# switch-pth-20mm-mk-1_0.net
KiCad netlist of a schematic drawn in EAGLE
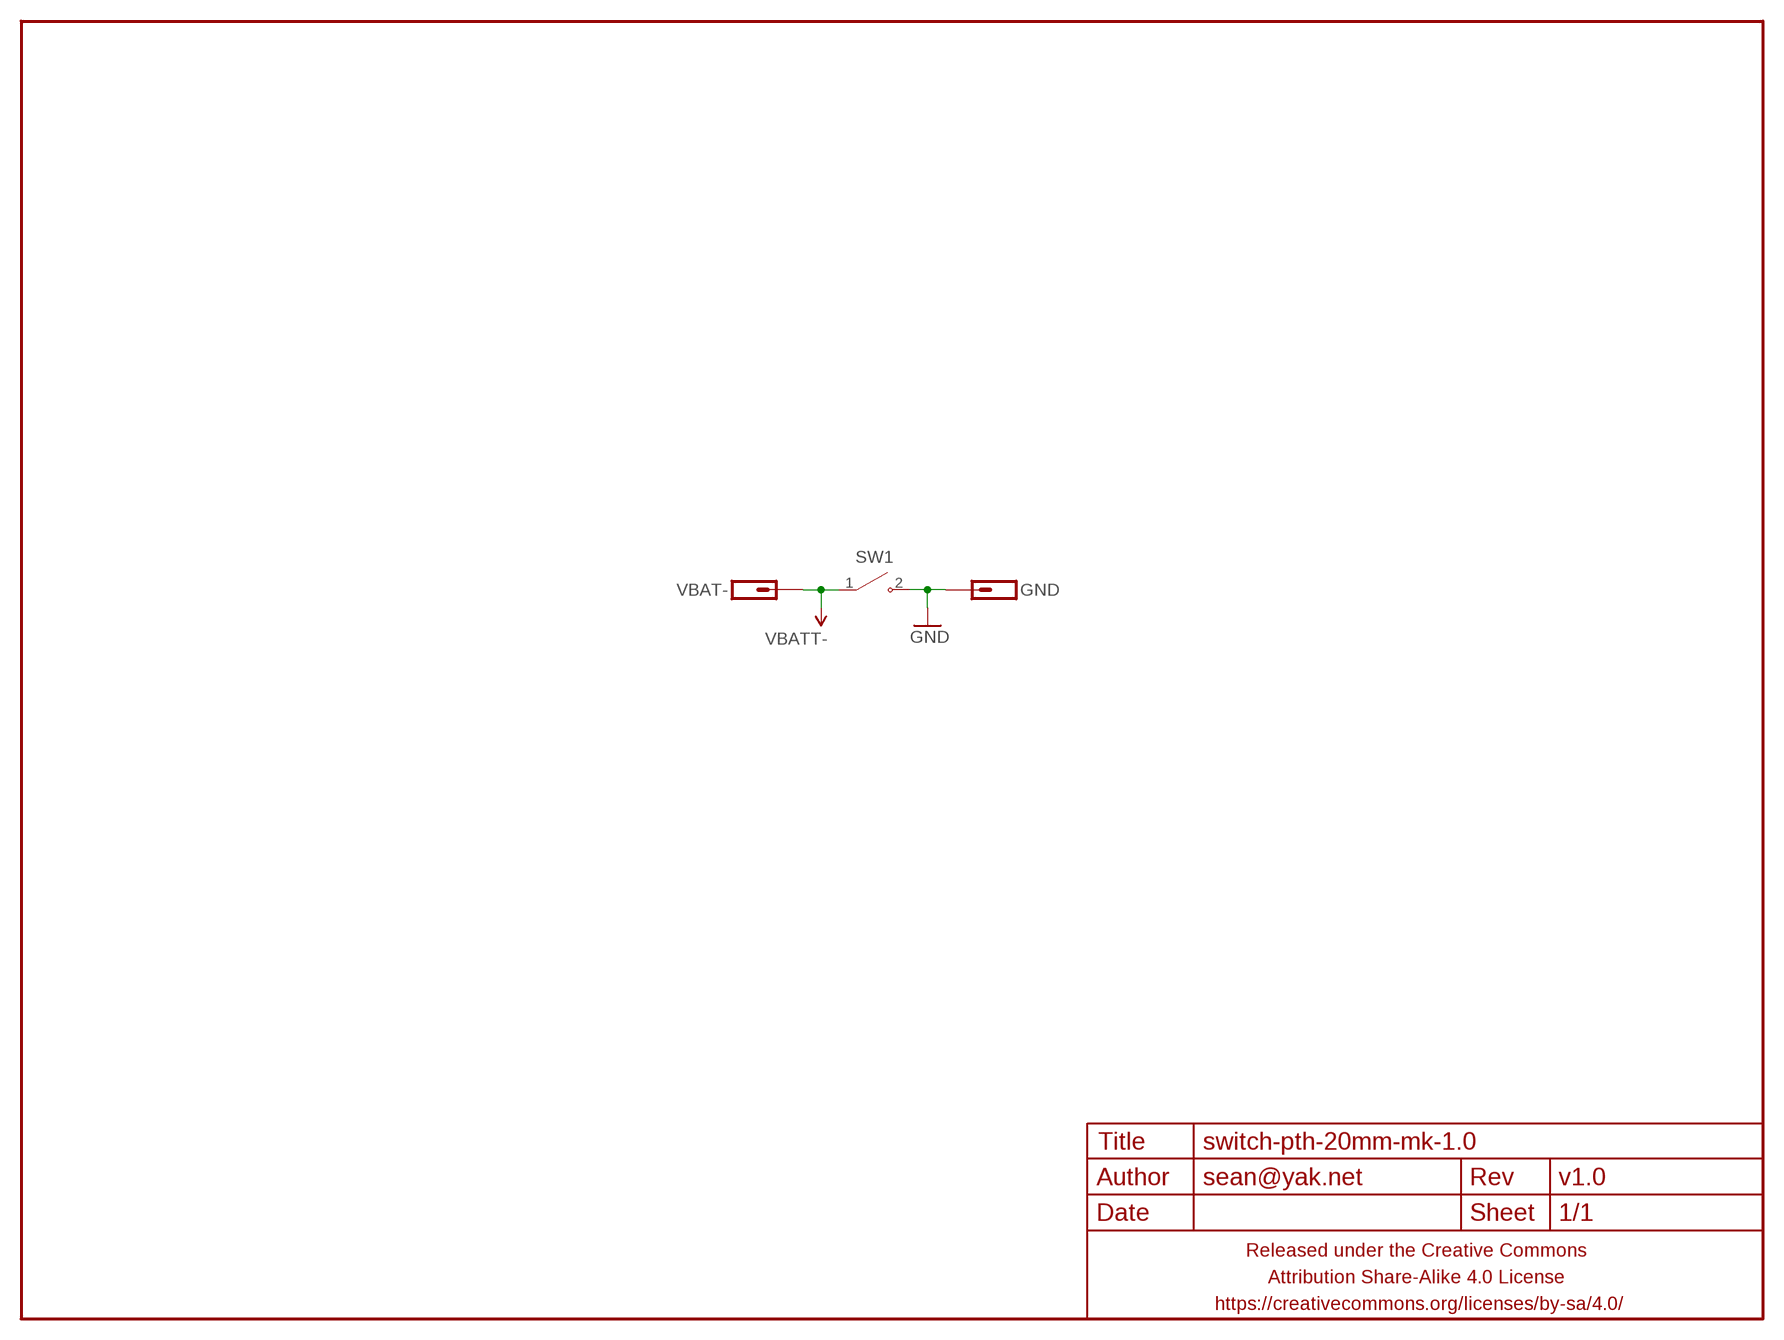
[diagram p0: schematic, sheet 1]

(export (version "E")
  (design (tool "Eeschema 10.0.6"))
  (components
    (comp (ref "FRAME1")
      (value "FRAME-LETTERNO_PACKAGE")
      (footprint "eagle-import:DUMMY")
      (fields (field (name "DESIGNER") "sean@yak.net") (field (name "VERSION") "v1.0"))
      (libsource (lib "eagle-import") (part "FRAME-LETTERNO_PACKAGE"))
    )
    (comp (ref "GND")
      (value "M01NOT-A-VIA-NOPE")
      (footprint "eagle-import:1X01_NOSILK_NOSTOP")
      (libsource (lib "eagle-import") (part "M01NOT-A-VIA-NOPE"))
    )
    (comp (ref "SW1")
      (value "SWITCH-SPSTOMTEN-1288-PTH")
      (footprint "eagle-import:OMTEN-1288-PTH")
      (libsource (lib "eagle-import") (part "SWITCH-SPSTOMTEN-1288-PTH"))
    )
    (comp (ref "VBAT-")
      (value "M01PTH-1MM-CIR-NS")
      (footprint "eagle-import:1X01-1MM-CIR-NS")
      (libsource (lib "eagle-import") (part "M01PTH-1MM-CIR-NS"))
    )
  )
  (nets
    (net (code "1") (name "GND") (class "Default")
      (node (ref "GND") (pin "P$1") (pinfunction "1_P$1") (pintype "passive"))
      (node (ref "SW1") (pin "2") (pinfunction "NO_2") (pintype "bidirectional"))
    )
    (net (code "2") (name "VBATT-") (class "Default")
      (node (ref "SW1") (pin "1") (pinfunction "COM_1") (pintype "bidirectional"))
      (node (ref "VBAT-") (pin "1") (pinfunction "1_1") (pintype "passive"))
    )
  )
)
